# adi-interface_v2.net
KiCad netlist of a schematic drawn in EAGLE
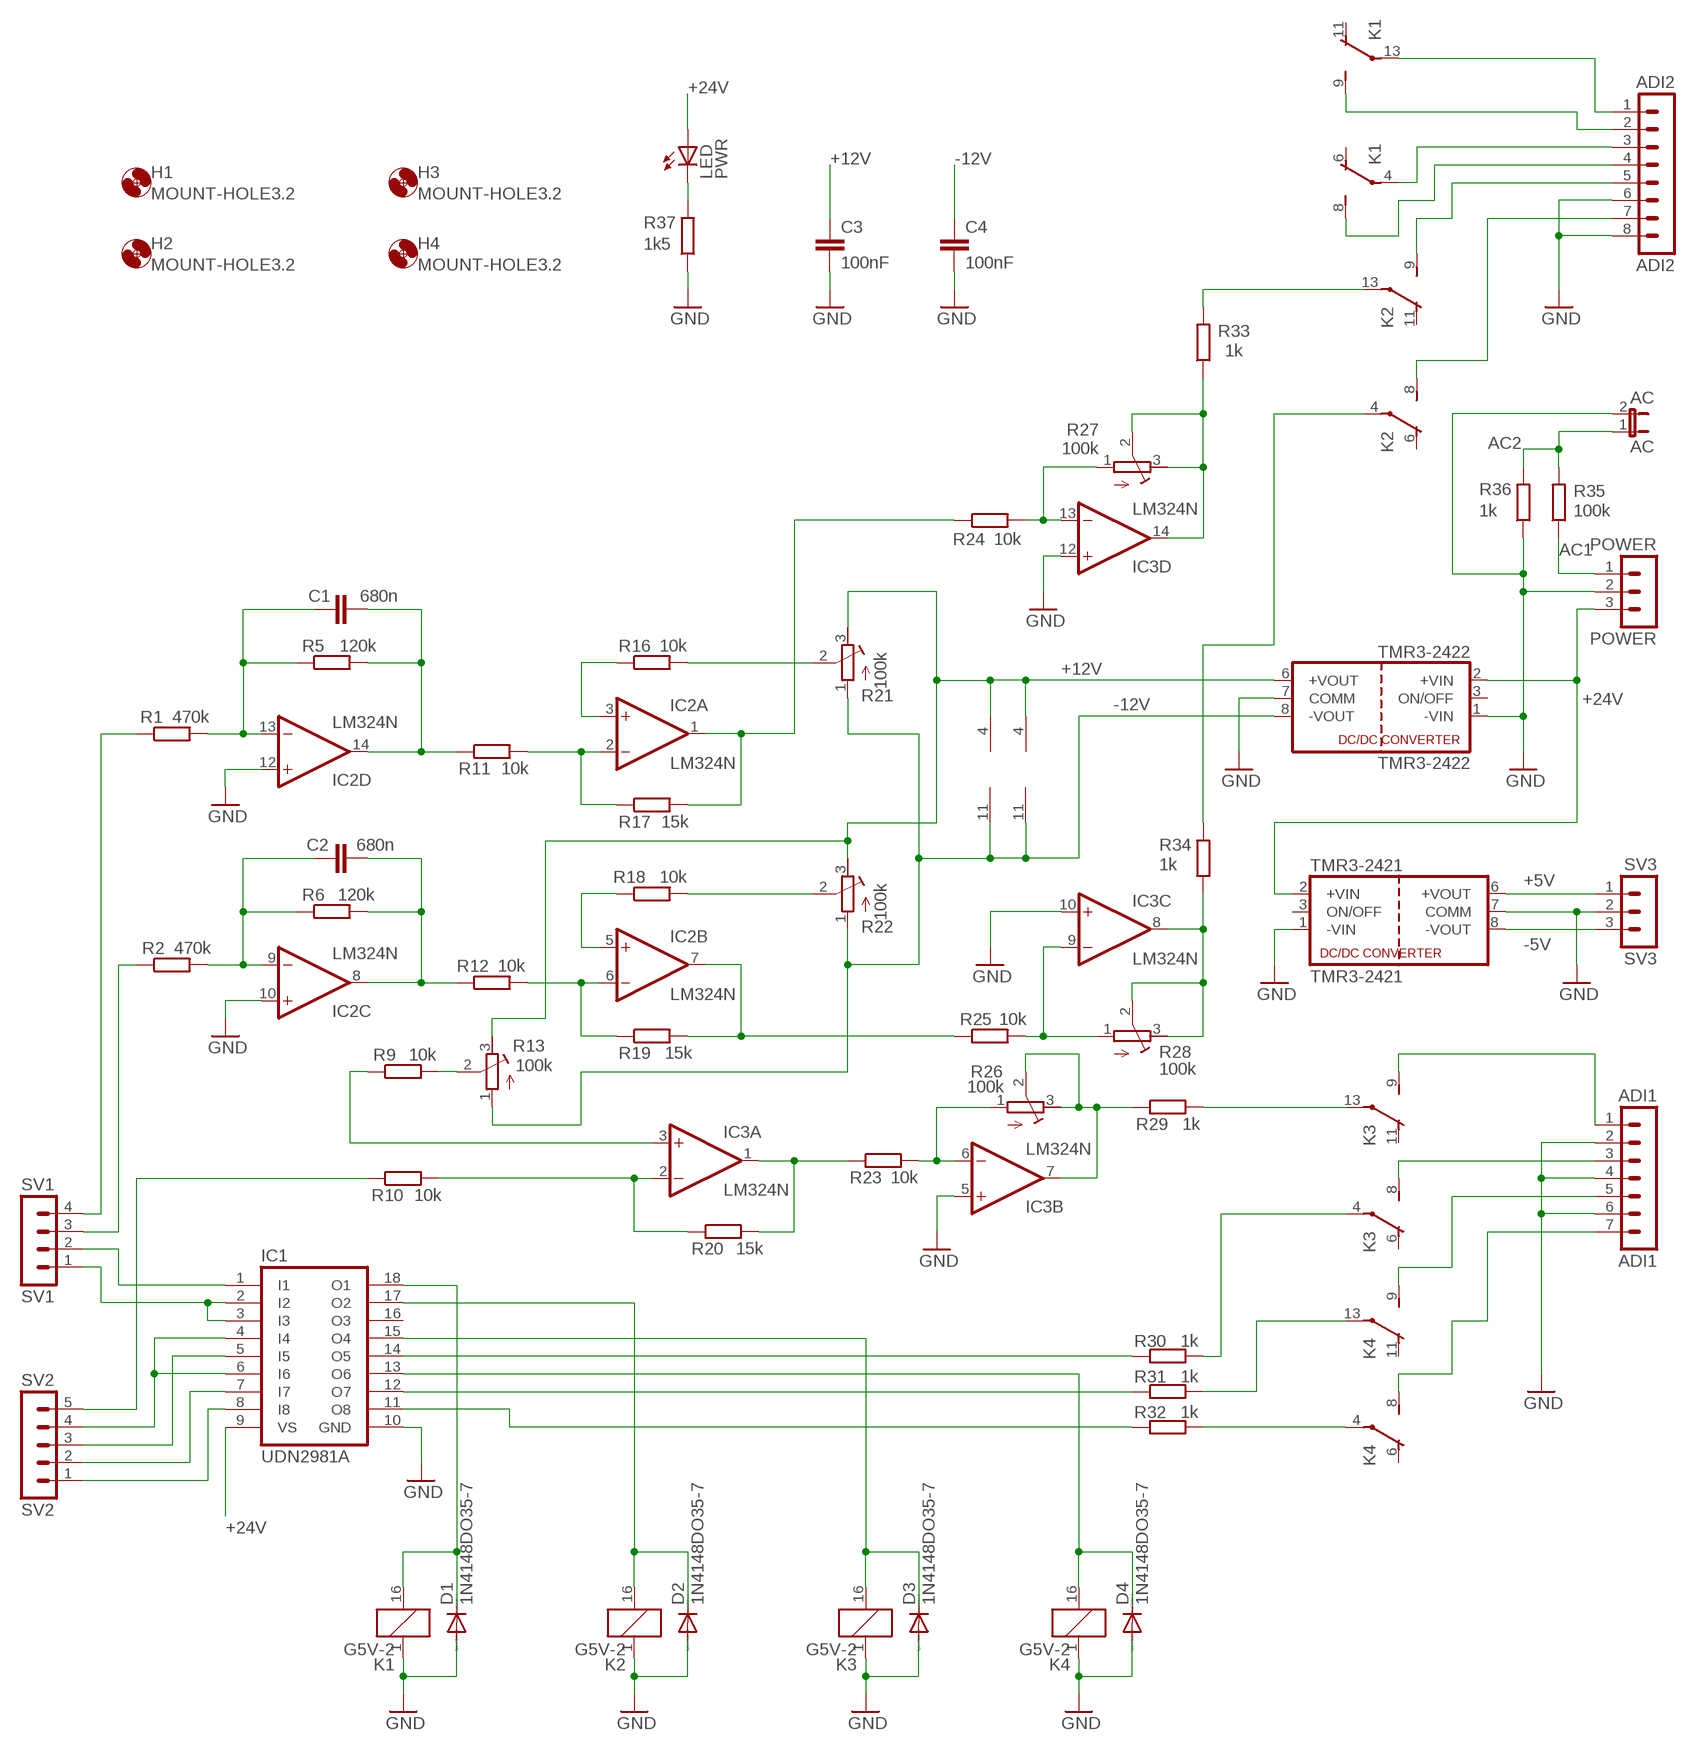
[diagram p0: schematic, sheet 1]
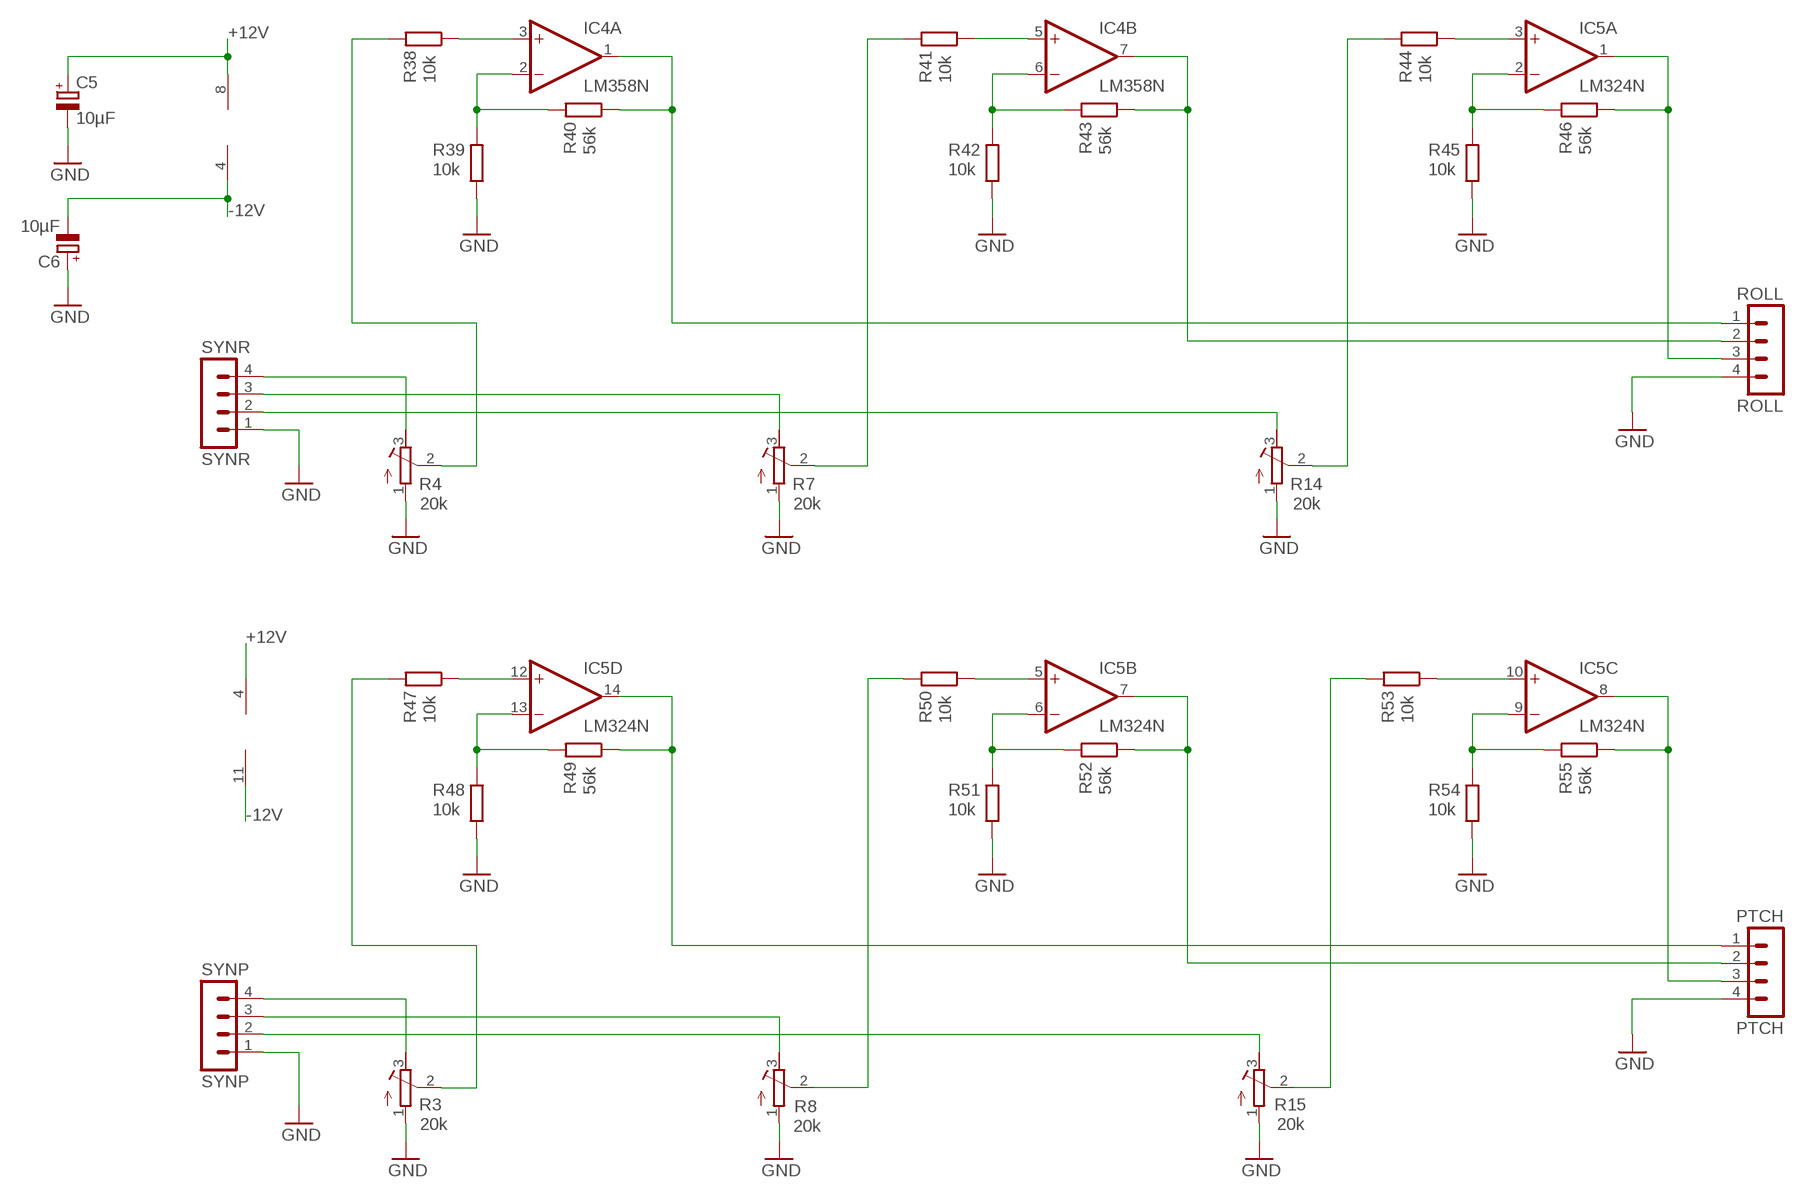
[diagram p1: schematic, sheet 2]

(export (version "E")
  (design (tool "Eeschema 10.0.6"))
  (components
    (comp (ref "AC")
      (value "AC")
      (footprint "eagle-import:1X02")
      (libsource (lib "eagle-import") (part "JUMPER-2PTH"))
    )
    (comp (ref "ADI1")
      (value "ADI1")
      (footprint "eagle-import:MA07-1")
      (libsource (lib "eagle-import") (part "MA07-1"))
    )
    (comp (ref "ADI2")
      (value "ADI2")
      (footprint "eagle-import:MA08-1")
      (libsource (lib "eagle-import") (part "MA08-1"))
    )
    (comp (ref "C1")
      (value "680n")
      (footprint "eagle-import:C050-035X075")
      (libsource (lib "eagle-import") (part "C-EU050-035X075"))
    )
    (comp (ref "C2")
      (value "680n")
      (footprint "eagle-import:C050-035X075")
      (libsource (lib "eagle-import") (part "C-EU050-035X075"))
    )
    (comp (ref "C3")
      (value "100nF")
      (footprint "eagle-import:C025-024X044")
      (libsource (lib "eagle-import") (part "C-EU025-024X044"))
    )
    (comp (ref "C4")
      (value "100nF")
      (footprint "eagle-import:C025-024X044")
      (libsource (lib "eagle-import") (part "C-EU025-024X044"))
    )
    (comp (ref "D1")
      (value "1N4148DO35-7")
      (footprint "eagle-import:DO35-7")
      (libsource (lib "eagle-import") (part "1N4148DO35-7"))
    )
    (comp (ref "D2")
      (value "1N4148DO35-7")
      (footprint "eagle-import:DO35-7")
      (libsource (lib "eagle-import") (part "1N4148DO35-7"))
    )
    (comp (ref "D3")
      (value "1N4148DO35-7")
      (footprint "eagle-import:DO35-7")
      (libsource (lib "eagle-import") (part "1N4148DO35-7"))
    )
    (comp (ref "D4")
      (value "1N4148DO35-7")
      (footprint "eagle-import:DO35-7")
      (libsource (lib "eagle-import") (part "1N4148DO35-7"))
    )
    (comp (ref "H1")
      (value "MOUNT-HOLE3.2")
      (footprint "eagle-import:3,2")
      (libsource (lib "eagle-import") (part "MOUNT-HOLE3.2"))
    )
    (comp (ref "H2")
      (value "MOUNT-HOLE3.2")
      (footprint "eagle-import:3,2")
      (libsource (lib "eagle-import") (part "MOUNT-HOLE3.2"))
    )
    (comp (ref "H3")
      (value "MOUNT-HOLE3.2")
      (footprint "eagle-import:3,2")
      (libsource (lib "eagle-import") (part "MOUNT-HOLE3.2"))
    )
    (comp (ref "H4")
      (value "MOUNT-HOLE3.2")
      (footprint "eagle-import:3,2")
      (libsource (lib "eagle-import") (part "MOUNT-HOLE3.2"))
    )
    (comp (ref "IC1")
      (value "UDN2981A")
      (footprint "eagle-import:DIL18")
      (libsource (lib "eagle-import") (part "UDN298A1"))
    )
    (comp (ref "IC2")
      (value "LM324N")
      (footprint "eagle-import:DIL14")
      (libsource (lib "eagle-import") (part "LM324N"))
    )
    (comp (ref "IC3")
      (value "LM324N")
      (footprint "eagle-import:DIL14")
      (libsource (lib "eagle-import") (part "LM324N"))
    )
    (comp (ref "K1")
      (value "G5V-2")
      (footprint "eagle-import:G5V-2")
      (fields (field (name "MPN") "G5V-2 5DC"))
      (libsource (lib "eagle-import") (part "G5V-2"))
    )
    (comp (ref "K2")
      (value "G5V-2")
      (footprint "eagle-import:G5V-2")
      (fields (field (name "MPN") "G5V-2 5DC"))
      (libsource (lib "eagle-import") (part "G5V-2"))
    )
    (comp (ref "K3")
      (value "G5V-2")
      (footprint "eagle-import:G5V-2")
      (fields (field (name "MPN") "G5V-2 5DC"))
      (libsource (lib "eagle-import") (part "G5V-2"))
    )
    (comp (ref "K4")
      (value "G5V-2")
      (footprint "eagle-import:G5V-2")
      (fields (field (name "MPN") "G5V-2 5DC"))
      (libsource (lib "eagle-import") (part "G5V-2"))
    )
    (comp (ref "LED")
      (value "PWR")
      (footprint "eagle-import:LED3MM")
      (libsource (lib "eagle-import") (part "LED3MM"))
    )
    (comp (ref "POWER")
      (value "POWER")
      (footprint "eagle-import:MA03-1")
      (libsource (lib "eagle-import") (part "MA03-1"))
    )
    (comp (ref "R1")
      (value "470k")
      (footprint "eagle-import:0204_7")
      (libsource (lib "eagle-import") (part "R-EU_0204/7"))
    )
    (comp (ref "R2")
      (value "470k")
      (footprint "eagle-import:0204_7")
      (libsource (lib "eagle-import") (part "R-EU_0204/7"))
    )
    (comp (ref "R5")
      (value "120k")
      (footprint "eagle-import:0204_7")
      (libsource (lib "eagle-import") (part "R-EU_0204/7"))
    )
    (comp (ref "R6")
      (value "120k")
      (footprint "eagle-import:0204_7")
      (libsource (lib "eagle-import") (part "R-EU_0204/7"))
    )
    (comp (ref "R9")
      (value "10k")
      (footprint "eagle-import:0204_7")
      (libsource (lib "eagle-import") (part "R-EU_0204/7"))
    )
    (comp (ref "R10")
      (value "10k")
      (footprint "eagle-import:0204_7")
      (libsource (lib "eagle-import") (part "R-EU_0204/7"))
    )
    (comp (ref "R11")
      (value "10k")
      (footprint "eagle-import:0204_7")
      (libsource (lib "eagle-import") (part "R-EU_0204/7"))
    )
    (comp (ref "R12")
      (value "10k")
      (footprint "eagle-import:0204_7")
      (libsource (lib "eagle-import") (part "R-EU_0204/7"))
    )
    (comp (ref "R13")
      (value "100k")
      (footprint "eagle-import:RTRIM64Z")
      (libsource (lib "eagle-import") (part "R-TRIMM64Z"))
    )
    (comp (ref "R16")
      (value "10k")
      (footprint "eagle-import:0204_7")
      (libsource (lib "eagle-import") (part "R-EU_0204/7"))
    )
    (comp (ref "R17")
      (value "15k")
      (footprint "eagle-import:0204_7")
      (libsource (lib "eagle-import") (part "R-EU_0204/7"))
    )
    (comp (ref "R18")
      (value "10k")
      (footprint "eagle-import:0204_7")
      (libsource (lib "eagle-import") (part "R-EU_0204/7"))
    )
    (comp (ref "R19")
      (value "15k")
      (footprint "eagle-import:0204_7")
      (libsource (lib "eagle-import") (part "R-EU_0204/7"))
    )
    (comp (ref "R20")
      (value "15k")
      (footprint "eagle-import:0204_7")
      (libsource (lib "eagle-import") (part "R-EU_0204/7"))
    )
    (comp (ref "R21")
      (value "100k")
      (footprint "eagle-import:RTRIM64Z")
      (libsource (lib "eagle-import") (part "R-TRIMM64Z"))
    )
    (comp (ref "R22")
      (value "100k")
      (footprint "eagle-import:RTRIM64Z")
      (libsource (lib "eagle-import") (part "R-TRIMM64Z"))
    )
    (comp (ref "R23")
      (value "10k")
      (footprint "eagle-import:0204_7")
      (libsource (lib "eagle-import") (part "R-EU_0204/7"))
    )
    (comp (ref "R24")
      (value "10k")
      (footprint "eagle-import:0204_7")
      (libsource (lib "eagle-import") (part "R-EU_0204/7"))
    )
    (comp (ref "R25")
      (value "10k")
      (footprint "eagle-import:0204_7")
      (libsource (lib "eagle-import") (part "R-EU_0204/7"))
    )
    (comp (ref "R26")
      (value "100k")
      (footprint "eagle-import:RTRIM64Z")
      (libsource (lib "eagle-import") (part "R-TRIMM64Z"))
    )
    (comp (ref "R27")
      (value "100k")
      (footprint "eagle-import:RTRIM64Z")
      (libsource (lib "eagle-import") (part "R-TRIMM64Z"))
    )
    (comp (ref "R28")
      (value "100k")
      (footprint "eagle-import:RTRIM64Z")
      (libsource (lib "eagle-import") (part "R-TRIMM64Z"))
    )
    (comp (ref "R29")
      (value "1k")
      (footprint "eagle-import:0204_7")
      (libsource (lib "eagle-import") (part "R-EU_0204/7"))
    )
    (comp (ref "R30")
      (value "1k")
      (footprint "eagle-import:0204_7")
      (libsource (lib "eagle-import") (part "R-EU_0204/7"))
    )
    (comp (ref "R31")
      (value "1k")
      (footprint "eagle-import:0204_7")
      (libsource (lib "eagle-import") (part "R-EU_0204/7"))
    )
    (comp (ref "R32")
      (value "1k")
      (footprint "eagle-import:0204_7")
      (libsource (lib "eagle-import") (part "R-EU_0204/7"))
    )
    (comp (ref "R33")
      (value "1k")
      (footprint "eagle-import:0204_7")
      (libsource (lib "eagle-import") (part "R-EU_0204/7"))
    )
    (comp (ref "R34")
      (value "1k")
      (footprint "eagle-import:0204_7")
      (libsource (lib "eagle-import") (part "R-EU_0204/7"))
    )
    (comp (ref "R35")
      (value "100k")
      (footprint "eagle-import:0204_7")
      (libsource (lib "eagle-import") (part "R-EU_0204/7"))
    )
    (comp (ref "R36")
      (value "1k")
      (footprint "eagle-import:0204_7")
      (libsource (lib "eagle-import") (part "R-EU_0204/7"))
    )
    (comp (ref "R37")
      (value "1k5")
      (footprint "eagle-import:0204_7")
      (libsource (lib "eagle-import") (part "R-EU_0204/7"))
    )
    (comp (ref "SV1")
      (value "SV1")
      (footprint "eagle-import:MA04-1")
      (libsource (lib "eagle-import") (part "MA04-1"))
    )
    (comp (ref "SV2")
      (value "SV2")
      (footprint "eagle-import:MA05-1")
      (libsource (lib "eagle-import") (part "MA05-1"))
    )
    (comp (ref "SV3")
      (value "SV3")
      (footprint "eagle-import:MA03-1")
      (libsource (lib "eagle-import") (part "MA03-1"))
    )
    (comp (ref "TMR3-2421")
      (value "TMR3-2421")
      (footprint "eagle-import:TRACO_SIP-8")
      (libsource (lib "eagle-import") (part "TMR"))
    )
    (comp (ref "TMR3-2422")
      (value "TMR3-2422")
      (footprint "eagle-import:TRACO_SIP-8")
      (libsource (lib "eagle-import") (part "TMR"))
    )
    (comp (ref "C5")
      (value "10µF")
      (footprint "eagle-import:E2,5-5")
      (libsource (lib "eagle-import") (part "CPOL-EUE2.5-5"))
    )
    (comp (ref "C6")
      (value "10µF")
      (footprint "eagle-import:E2,5-5")
      (libsource (lib "eagle-import") (part "CPOL-EUE2.5-5"))
    )
    (comp (ref "IC4")
      (value "LM358N")
      (footprint "eagle-import:DIL08")
      (libsource (lib "eagle-import") (part "LM358N"))
    )
    (comp (ref "IC5")
      (value "LM324N")
      (footprint "eagle-import:DIL14")
      (libsource (lib "eagle-import") (part "LM324N"))
    )
    (comp (ref "PTCH")
      (value "PTCH")
      (footprint "eagle-import:MA04-1")
      (libsource (lib "eagle-import") (part "MA04-1"))
    )
    (comp (ref "R3")
      (value "20k")
      (footprint "eagle-import:RTRIM64Z")
      (libsource (lib "eagle-import") (part "R-TRIMM64Z"))
    )
    (comp (ref "R4")
      (value "20k")
      (footprint "eagle-import:RTRIM64Z")
      (libsource (lib "eagle-import") (part "R-TRIMM64Z"))
    )
    (comp (ref "R7")
      (value "20k")
      (footprint "eagle-import:RTRIM64Z")
      (libsource (lib "eagle-import") (part "R-TRIMM64Z"))
    )
    (comp (ref "R8")
      (value "20k")
      (footprint "eagle-import:RTRIM64Z")
      (libsource (lib "eagle-import") (part "R-TRIMM64Z"))
    )
    (comp (ref "R14")
      (value "20k")
      (footprint "eagle-import:RTRIM64Z")
      (libsource (lib "eagle-import") (part "R-TRIMM64Z"))
    )
    (comp (ref "R15")
      (value "20k")
      (footprint "eagle-import:RTRIM64Z")
      (libsource (lib "eagle-import") (part "R-TRIMM64Z"))
    )
    (comp (ref "R38")
      (value "10k")
      (footprint "eagle-import:0204_7")
      (libsource (lib "eagle-import") (part "R-EU_0204/7"))
    )
    (comp (ref "R39")
      (value "10k")
      (footprint "eagle-import:0204_7")
      (libsource (lib "eagle-import") (part "R-EU_0204/7"))
    )
    (comp (ref "R40")
      (value "56k")
      (footprint "eagle-import:0204_7")
      (libsource (lib "eagle-import") (part "R-EU_0204/7"))
    )
    (comp (ref "R41")
      (value "10k")
      (footprint "eagle-import:0204_7")
      (libsource (lib "eagle-import") (part "R-EU_0204/7"))
    )
    (comp (ref "R42")
      (value "10k")
      (footprint "eagle-import:0204_7")
      (libsource (lib "eagle-import") (part "R-EU_0204/7"))
    )
    (comp (ref "R43")
      (value "56k")
      (footprint "eagle-import:0204_7")
      (libsource (lib "eagle-import") (part "R-EU_0204/7"))
    )
    (comp (ref "R44")
      (value "10k")
      (footprint "eagle-import:0204_7")
      (libsource (lib "eagle-import") (part "R-EU_0204/7"))
    )
    (comp (ref "R45")
      (value "10k")
      (footprint "eagle-import:0204_7")
      (libsource (lib "eagle-import") (part "R-EU_0204/7"))
    )
    (comp (ref "R46")
      (value "56k")
      (footprint "eagle-import:0204_7")
      (libsource (lib "eagle-import") (part "R-EU_0204/7"))
    )
    (comp (ref "R47")
      (value "10k")
      (footprint "eagle-import:0204_7")
      (libsource (lib "eagle-import") (part "R-EU_0204/7"))
    )
    (comp (ref "R48")
      (value "10k")
      (footprint "eagle-import:0204_7")
      (libsource (lib "eagle-import") (part "R-EU_0204/7"))
    )
    (comp (ref "R49")
      (value "56k")
      (footprint "eagle-import:0204_7")
      (libsource (lib "eagle-import") (part "R-EU_0204/7"))
    )
    (comp (ref "R50")
      (value "10k")
      (footprint "eagle-import:0204_7")
      (libsource (lib "eagle-import") (part "R-EU_0204/7"))
    )
    (comp (ref "R51")
      (value "10k")
      (footprint "eagle-import:0204_7")
      (libsource (lib "eagle-import") (part "R-EU_0204/7"))
    )
    (comp (ref "R52")
      (value "56k")
      (footprint "eagle-import:0204_7")
      (libsource (lib "eagle-import") (part "R-EU_0204/7"))
    )
    (comp (ref "R53")
      (value "10k")
      (footprint "eagle-import:0204_7")
      (libsource (lib "eagle-import") (part "R-EU_0204/7"))
    )
    (comp (ref "R54")
      (value "10k")
      (footprint "eagle-import:0204_7")
      (libsource (lib "eagle-import") (part "R-EU_0204/7"))
    )
    (comp (ref "R55")
      (value "56k")
      (footprint "eagle-import:0204_7")
      (libsource (lib "eagle-import") (part "R-EU_0204/7"))
    )
    (comp (ref "ROLL")
      (value "ROLL")
      (footprint "eagle-import:MA04-1")
      (libsource (lib "eagle-import") (part "MA04-1"))
    )
    (comp (ref "SYNP")
      (value "SYNP")
      (footprint "eagle-import:MA04-1")
      (libsource (lib "eagle-import") (part "MA04-1"))
    )
    (comp (ref "SYNR")
      (value "SYNR")
      (footprint "eagle-import:MA04-1")
      (libsource (lib "eagle-import") (part "MA04-1"))
    )
  )
  (nets
    (net (code "1") (name "+5V") (class "Default")
      (node (ref "SV3") (pin "1") (pinfunction "1_1") (pintype "passive"))
      (node (ref "TMR3-2421") (pin "6") (pinfunction "+VOUT_6") (pintype "passive"))
    )
    (net (code "2") (name "+12V") (class "Default")
      (node (ref "C3") (pin "1") (pinfunction "1_1") (pintype "passive"))
      (node (ref "C5") (pin "+") (pinfunction "+_+") (pintype "passive"))
      (node (ref "IC2") (pin "4") (pinfunction "V+_4") (pintype "power_in"))
      (node (ref "IC3") (pin "4") (pinfunction "V+_4") (pintype "power_in"))
      (node (ref "IC4") (pin "8") (pinfunction "V+_8") (pintype "power_in"))
      (node (ref "IC5") (pin "4") (pinfunction "V+_4") (pintype "power_in"))
      (node (ref "R13") (pin "3") (pinfunction "E_3") (pintype "passive"))
      (node (ref "R21") (pin "3") (pinfunction "E_3") (pintype "passive"))
      (node (ref "R22") (pin "3") (pinfunction "E_3") (pintype "passive"))
      (node (ref "TMR3-2422") (pin "6") (pinfunction "+VOUT_6") (pintype "passive"))
    )
    (net (code "3") (name "+24V") (class "Default")
      (node (ref "IC1") (pin "9") (pinfunction "VS_9") (pintype "passive"))
      (node (ref "LED") (pin "A") (pinfunction "A_A") (pintype "passive"))
      (node (ref "POWER") (pin "3") (pinfunction "3_3") (pintype "passive"))
      (node (ref "TMR3-2421") (pin "2") (pinfunction "+VIN_2") (pintype "passive"))
      (node (ref "TMR3-2422") (pin "2") (pinfunction "+VIN_2") (pintype "passive"))
    )
    (net (code "4") (name "-5V") (class "Default")
      (node (ref "SV3") (pin "3") (pinfunction "3_3") (pintype "passive"))
      (node (ref "TMR3-2421") (pin "8") (pinfunction "-VOUT_8") (pintype "passive"))
    )
    (net (code "5") (name "-12V") (class "Default")
      (node (ref "C4") (pin "1") (pinfunction "1_1") (pintype "passive"))
      (node (ref "C6") (pin "-") (pinfunction "-_-") (pintype "passive"))
      (node (ref "IC2") (pin "11") (pinfunction "V-_11") (pintype "power_in"))
      (node (ref "IC3") (pin "11") (pinfunction "V-_11") (pintype "power_in"))
      (node (ref "IC4") (pin "4") (pinfunction "V-_4") (pintype "power_in"))
      (node (ref "IC5") (pin "11") (pinfunction "V-_11") (pintype "power_in"))
      (node (ref "R13") (pin "1") (pinfunction "A_1") (pintype "passive"))
      (node (ref "R21") (pin "1") (pinfunction "A_1") (pintype "passive"))
      (node (ref "R22") (pin "1") (pinfunction "A_1") (pintype "passive"))
      (node (ref "TMR3-2422") (pin "8") (pinfunction "-VOUT_8") (pintype "passive"))
    )
    (net (code "6") (name "AC1") (class "Default")
      (node (ref "POWER") (pin "1") (pinfunction "1_1") (pintype "passive"))
      (node (ref "R35") (pin "1") (pinfunction "1_1") (pintype "passive"))
    )
    (net (code "7") (name "AC2") (class "Default")
      (node (ref "AC") (pin "1") (pinfunction "1_1") (pintype "passive"))
      (node (ref "R35") (pin "2") (pinfunction "2_2") (pintype "passive"))
      (node (ref "R36") (pin "2") (pinfunction "2_2") (pintype "passive"))
    )
    (net (code "8") (name "GND") (class "Default")
      (node (ref "AC") (pin "2") (pinfunction "2_2") (pintype "passive"))
      (node (ref "ADI1") (pin "2") (pinfunction "2_2") (pintype "passive"))
      (node (ref "ADI1") (pin "4") (pinfunction "4_4") (pintype "passive"))
      (node (ref "ADI1") (pin "6") (pinfunction "6_6") (pintype "passive"))
      (node (ref "ADI2") (pin "6") (pinfunction "6_6") (pintype "passive"))
      (node (ref "ADI2") (pin "8") (pinfunction "8_8") (pintype "passive"))
      (node (ref "C3") (pin "2") (pinfunction "2_2") (pintype "passive"))
      (node (ref "C4") (pin "2") (pinfunction "2_2") (pintype "passive"))
      (node (ref "C5") (pin "-") (pinfunction "-_-") (pintype "passive"))
      (node (ref "C6") (pin "+") (pinfunction "+_+") (pintype "passive"))
      (node (ref "D1") (pin "A") (pinfunction "A_A") (pintype "passive"))
      (node (ref "D2") (pin "A") (pinfunction "A_A") (pintype "passive"))
      (node (ref "D3") (pin "A") (pinfunction "A_A") (pintype "passive"))
      (node (ref "D4") (pin "A") (pinfunction "A_A") (pintype "passive"))
      (node (ref "IC1") (pin "10") (pinfunction "GND_10") (pintype "power_in"))
      (node (ref "IC2") (pin "10") (pinfunction "+IN_10") (pintype "input"))
      (node (ref "IC2") (pin "12") (pinfunction "+IN_12") (pintype "input"))
      (node (ref "IC3") (pin "10") (pinfunction "+IN_10") (pintype "input"))
      (node (ref "IC3") (pin "12") (pinfunction "+IN_12") (pintype "input"))
      (node (ref "IC3") (pin "5") (pinfunction "+IN_5") (pintype "input"))
      (node (ref "K1") (pin "1") (pinfunction "1_1") (pintype "passive"))
      (node (ref "K2") (pin "1") (pinfunction "1_1") (pintype "passive"))
      (node (ref "K3") (pin "1") (pinfunction "1_1") (pintype "passive"))
      (node (ref "K4") (pin "1") (pinfunction "1_1") (pintype "passive"))
      (node (ref "POWER") (pin "2") (pinfunction "2_2") (pintype "passive"))
      (node (ref "PTCH") (pin "4") (pinfunction "4_4") (pintype "passive"))
      (node (ref "R14") (pin "1") (pinfunction "A_1") (pintype "passive"))
      (node (ref "R15") (pin "1") (pinfunction "A_1") (pintype "passive"))
      (node (ref "R3") (pin "1") (pinfunction "A_1") (pintype "passive"))
      (node (ref "R36") (pin "1") (pinfunction "1_1") (pintype "passive"))
      (node (ref "R37") (pin "1") (pinfunction "1_1") (pintype "passive"))
      (node (ref "R39") (pin "1") (pinfunction "1_1") (pintype "passive"))
      (node (ref "R4") (pin "1") (pinfunction "A_1") (pintype "passive"))
      (node (ref "R42") (pin "1") (pinfunction "1_1") (pintype "passive"))
      (node (ref "R45") (pin "1") (pinfunction "1_1") (pintype "passive"))
      (node (ref "R48") (pin "1") (pinfunction "1_1") (pintype "passive"))
      (node (ref "R51") (pin "1") (pinfunction "1_1") (pintype "passive"))
      (node (ref "R54") (pin "1") (pinfunction "1_1") (pintype "passive"))
      (node (ref "R7") (pin "1") (pinfunction "A_1") (pintype "passive"))
      (node (ref "R8") (pin "1") (pinfunction "A_1") (pintype "passive"))
      (node (ref "ROLL") (pin "4") (pinfunction "4_4") (pintype "passive"))
      (node (ref "SV3") (pin "2") (pinfunction "2_2") (pintype "passive"))
      (node (ref "SYNP") (pin "1") (pinfunction "1_1") (pintype "passive"))
      (node (ref "SYNR") (pin "1") (pinfunction "1_1") (pintype "passive"))
      (node (ref "TMR3-2421") (pin "1") (pinfunction "-VIN_1") (pintype "passive"))
      (node (ref "TMR3-2421") (pin "7") (pinfunction "COMM_7") (pintype "passive"))
      (node (ref "TMR3-2422") (pin "1") (pinfunction "-VIN_1") (pintype "passive"))
      (node (ref "TMR3-2422") (pin "7") (pinfunction "COMM_7") (pintype "passive"))
    )
    (net (code "9") (name "Net-(IC1-I1)") (class "Default")
      (node (ref "IC1") (pin "1") (pinfunction "I1_1") (pintype "input"))
      (node (ref "SV1") (pin "2") (pinfunction "2_2") (pintype "passive"))
    )
    (net (code "10") (name "Net-(IC1-I2)") (class "Default")
      (node (ref "IC1") (pin "2") (pinfunction "I2_2") (pintype "input"))
      (node (ref "IC1") (pin "3") (pinfunction "I3_3") (pintype "input"))
      (node (ref "SV1") (pin "1") (pinfunction "1_1") (pintype "passive"))
    )
    (net (code "11") (name "Net-(IC1-I4)") (class "Default")
      (node (ref "IC1") (pin "4") (pinfunction "I4_4") (pintype "input"))
      (node (ref "IC1") (pin "6") (pinfunction "I6_6") (pintype "input"))
      (node (ref "SV2") (pin "4") (pinfunction "4_4") (pintype "passive"))
    )
    (net (code "12") (name "Net-(IC1-I5)") (class "Default")
      (node (ref "IC1") (pin "5") (pinfunction "I5_5") (pintype "input"))
      (node (ref "SV2") (pin "3") (pinfunction "3_3") (pintype "passive"))
    )
    (net (code "13") (name "Net-(IC1-I7)") (class "Default")
      (node (ref "IC1") (pin "7") (pinfunction "I7_7") (pintype "input"))
      (node (ref "SV2") (pin "2") (pinfunction "2_2") (pintype "passive"))
    )
    (net (code "14") (name "Net-(IC1-I8)") (class "Default")
      (node (ref "IC1") (pin "8") (pinfunction "I8_8") (pintype "input"))
      (node (ref "SV2") (pin "1") (pinfunction "1_1") (pintype "passive"))
    )
    (net (code "15") (name "Net-(IC1-O1)") (class "Default")
      (node (ref "D1") (pin "C") (pinfunction "C_C") (pintype "passive"))
      (node (ref "IC1") (pin "18") (pinfunction "O1_18") (pintype "open_collector"))
      (node (ref "K1") (pin "16") (pinfunction "2_16") (pintype "passive"))
    )
    (net (code "16") (name "Net-(IC1-O2)") (class "Default")
      (node (ref "D2") (pin "C") (pinfunction "C_C") (pintype "passive"))
      (node (ref "IC1") (pin "17") (pinfunction "O2_17") (pintype "open_collector"))
      (node (ref "K2") (pin "16") (pinfunction "2_16") (pintype "passive"))
    )
    (net (code "17") (name "Net-(IC1-O4)") (class "Default")
      (node (ref "D3") (pin "C") (pinfunction "C_C") (pintype "passive"))
      (node (ref "IC1") (pin "15") (pinfunction "O4_15") (pintype "open_collector"))
      (node (ref "K3") (pin "16") (pinfunction "2_16") (pintype "passive"))
    )
    (net (code "18") (name "Net-(IC1-O5)") (class "Default")
      (node (ref "IC1") (pin "14") (pinfunction "O5_14") (pintype "open_collector"))
      (node (ref "R30") (pin "1") (pinfunction "1_1") (pintype "passive"))
    )
    (net (code "19") (name "Net-(IC1-O6)") (class "Default")
      (node (ref "D4") (pin "C") (pinfunction "C_C") (pintype "passive"))
      (node (ref "IC1") (pin "13") (pinfunction "O6_13") (pintype "open_collector"))
      (node (ref "K4") (pin "16") (pinfunction "2_16") (pintype "passive"))
    )
    (net (code "20") (name "Net-(IC1-O7)") (class "Default")
      (node (ref "IC1") (pin "12") (pinfunction "O7_12") (pintype "open_collector"))
      (node (ref "R31") (pin "1") (pinfunction "1_1") (pintype "passive"))
    )
    (net (code "21") (name "Net-(IC1-O8)") (class "Default")
      (node (ref "IC1") (pin "11") (pinfunction "O8_11") (pintype "open_collector"))
      (node (ref "R32") (pin "1") (pinfunction "1_1") (pintype "passive"))
    )
    (net (code "22") (name "Net-(IC2A-+IN)") (class "Default")
      (node (ref "IC2") (pin "3") (pinfunction "+IN_3") (pintype "input"))
      (node (ref "R16") (pin "1") (pinfunction "1_1") (pintype "passive"))
    )
    (net (code "23") (name "Net-(IC2A--IN)") (class "Default")
      (node (ref "IC2") (pin "2") (pinfunction "-IN_2") (pintype "input"))
      (node (ref "R11") (pin "2") (pinfunction "2_2") (pintype "passive"))
      (node (ref "R17") (pin "1") (pinfunction "1_1") (pintype "passive"))
    )
    (net (code "24") (name "Net-(IC2A-OUT)") (class "Default")
      (node (ref "IC2") (pin "1") (pinfunction "OUT_1") (pintype "output"))
      (node (ref "R17") (pin "2") (pinfunction "2_2") (pintype "passive"))
      (node (ref "R24") (pin "1") (pinfunction "1_1") (pintype "passive"))
    )
    (net (code "25") (name "Net-(IC2B-+IN)") (class "Default")
      (node (ref "IC2") (pin "5") (pinfunction "+IN_5") (pintype "input"))
      (node (ref "R18") (pin "1") (pinfunction "1_1") (pintype "passive"))
    )
    (net (code "26") (name "Net-(IC2B--IN)") (class "Default")
      (node (ref "IC2") (pin "6") (pinfunction "-IN_6") (pintype "input"))
      (node (ref "R12") (pin "2") (pinfunction "2_2") (pintype "passive"))
      (node (ref "R19") (pin "1") (pinfunction "1_1") (pintype "passive"))
    )
    (net (code "27") (name "Net-(IC2B-OUT)") (class "Default")
      (node (ref "IC2") (pin "7") (pinfunction "OUT_7") (pintype "output"))
      (node (ref "R19") (pin "2") (pinfunction "2_2") (pintype "passive"))
      (node (ref "R25") (pin "1") (pinfunction "1_1") (pintype "passive"))
    )
    (net (code "28") (name "Net-(IC2C--IN)") (class "Default")
      (node (ref "C2") (pin "1") (pinfunction "1_1") (pintype "passive"))
      (node (ref "IC2") (pin "9") (pinfunction "-IN_9") (pintype "input"))
      (node (ref "R2") (pin "2") (pinfunction "2_2") (pintype "passive"))
      (node (ref "R6") (pin "1") (pinfunction "1_1") (pintype "passive"))
    )
    (net (code "29") (name "Net-(IC2C-OUT)") (class "Default")
      (node (ref "C2") (pin "2") (pinfunction "2_2") (pintype "passive"))
      (node (ref "IC2") (pin "8") (pinfunction "OUT_8") (pintype "output"))
      (node (ref "R12") (pin "1") (pinfunction "1_1") (pintype "passive"))
      (node (ref "R6") (pin "2") (pinfunction "2_2") (pintype "passive"))
    )
    (net (code "30") (name "Net-(IC2D--IN)") (class "Default")
      (node (ref "C1") (pin "1") (pinfunction "1_1") (pintype "passive"))
      (node (ref "IC2") (pin "13") (pinfunction "-IN_13") (pintype "input"))
      (node (ref "R1") (pin "2") (pinfunction "2_2") (pintype "passive"))
      (node (ref "R5") (pin "1") (pinfunction "1_1") (pintype "passive"))
    )
    (net (code "31") (name "Net-(IC2D-OUT)") (class "Default")
      (node (ref "C1") (pin "2") (pinfunction "2_2") (pintype "passive"))
      (node (ref "IC2") (pin "14") (pinfunction "OUT_14") (pintype "output"))
      (node (ref "R11") (pin "1") (pinfunction "1_1") (pintype "passive"))
      (node (ref "R5") (pin "2") (pinfunction "2_2") (pintype "passive"))
    )
    (net (code "32") (name "Net-(IC3A-+IN)") (class "Default")
      (node (ref "IC3") (pin "3") (pinfunction "+IN_3") (pintype "input"))
      (node (ref "R9") (pin "1") (pinfunction "1_1") (pintype "passive"))
    )
    (net (code "33") (name "Net-(IC3A--IN)") (class "Default")
      (node (ref "IC3") (pin "2") (pinfunction "-IN_2") (pintype "input"))
      (node (ref "R10") (pin "2") (pinfunction "2_2") (pintype "passive"))
      (node (ref "R20") (pin "1") (pinfunction "1_1") (pintype "passive"))
    )
    (net (code "34") (name "Net-(IC3A-OUT)") (class "Default")
      (node (ref "IC3") (pin "1") (pinfunction "OUT_1") (pintype "output"))
      (node (ref "R20") (pin "2") (pinfunction "2_2") (pintype "passive"))
      (node (ref "R23") (pin "1") (pinfunction "1_1") (pintype "passive"))
    )
    (net (code "35") (name "Net-(IC3B--IN)") (class "Default")
      (node (ref "IC3") (pin "6") (pinfunction "-IN_6") (pintype "input"))
      (node (ref "R23") (pin "2") (pinfunction "2_2") (pintype "passive"))
      (node (ref "R26") (pin "1") (pinfunction "A_1") (pintype "passive"))
    )
    (net (code "36") (name "Net-(IC3B-OUT)") (class "Default")
      (node (ref "IC3") (pin "7") (pinfunction "OUT_7") (pintype "output"))
      (node (ref "R26") (pin "2") (pinfunction "S_2") (pintype "passive"))
      (node (ref "R26") (pin "3") (pinfunction "E_3") (pintype "passive"))
      (node (ref "R29") (pin "1") (pinfunction "1_1") (pintype "passive"))
    )
    (net (code "37") (name "Net-(IC3C--IN)") (class "Default")
      (node (ref "IC3") (pin "9") (pinfunction "-IN_9") (pintype "input"))
      (node (ref "R25") (pin "2") (pinfunction "2_2") (pintype "passive"))
      (node (ref "R28") (pin "1") (pinfunction "A_1") (pintype "passive"))
    )
    (net (code "38") (name "Net-(IC3C-OUT)") (class "Default")
      (node (ref "IC3") (pin "8") (pinfunction "OUT_8") (pintype "output"))
      (node (ref "R28") (pin "2") (pinfunction "S_2") (pintype "passive"))
      (node (ref "R28") (pin "3") (pinfunction "E_3") (pintype "passive"))
      (node (ref "R34") (pin "1") (pinfunction "1_1") (pintype "passive"))
    )
    (net (code "39") (name "Net-(IC3D--IN)") (class "Default")
      (node (ref "IC3") (pin "13") (pinfunction "-IN_13") (pintype "input"))
      (node (ref "R24") (pin "2") (pinfunction "2_2") (pintype "passive"))
      (node (ref "R27") (pin "1") (pinfunction "A_1") (pintype "passive"))
    )
    (net (code "40") (name "Net-(IC3D-OUT)") (class "Default")
      (node (ref "IC3") (pin "14") (pinfunction "OUT_14") (pintype "output"))
      (node (ref "R27") (pin "2") (pinfunction "S_2") (pintype "passive"))
      (node (ref "R27") (pin "3") (pinfunction "E_3") (pintype "passive"))
      (node (ref "R33") (pin "1") (pinfunction "1_1") (pintype "passive"))
    )
    (net (code "41") (name "Net-(IC4A-+IN)") (class "Default")
      (node (ref "IC4") (pin "3") (pinfunction "+IN_3") (pintype "input"))
      (node (ref "R38") (pin "1") (pinfunction "1_1") (pintype "passive"))
    )
    (net (code "42") (name "Net-(IC4A--IN)") (class "Default")
      (node (ref "IC4") (pin "2") (pinfunction "-IN_2") (pintype "input"))
      (node (ref "R39") (pin "2") (pinfunction "2_2") (pintype "passive"))
      (node (ref "R40") (pin "2") (pinfunction "2_2") (pintype "passive"))
    )
    (net (code "43") (name "Net-(IC4A-OUT)") (class "Default")
      (node (ref "IC4") (pin "1") (pinfunction "OUT_1") (pintype "output"))
      (node (ref "R40") (pin "1") (pinfunction "1_1") (pintype "passive"))
      (node (ref "ROLL") (pin "1") (pinfunction "1_1") (pintype "passive"))
    )
    (net (code "44") (name "Net-(IC4B-+IN)") (class "Default")
      (node (ref "IC4") (pin "5") (pinfunction "+IN_5") (pintype "input"))
      (node (ref "R41") (pin "1") (pinfunction "1_1") (pintype "passive"))
    )
    (net (code "45") (name "Net-(IC4B--IN)") (class "Default")
      (node (ref "IC4") (pin "6") (pinfunction "-IN_6") (pintype "input"))
      (node (ref "R42") (pin "2") (pinfunction "2_2") (pintype "passive"))
      (node (ref "R43") (pin "2") (pinfunction "2_2") (pintype "passive"))
    )
    (net (code "46") (name "Net-(IC4B-OUT)") (class "Default")
      (node (ref "IC4") (pin "7") (pinfunction "OUT_7") (pintype "output"))
      (node (ref "R43") (pin "1") (pinfunction "1_1") (pintype "passive"))
      (node (ref "ROLL") (pin "2") (pinfunction "2_2") (pintype "passive"))
    )
    (net (code "47") (name "Net-(IC5A-+IN)") (class "Default")
      (node (ref "IC5") (pin "3") (pinfunction "+IN_3") (pintype "input"))
      (node (ref "R44") (pin "1") (pinfunction "1_1") (pintype "passive"))
    )
    (net (code "48") (name "Net-(IC5A--IN)") (class "Default")
      (node (ref "IC5") (pin "2") (pinfunction "-IN_2") (pintype "input"))
      (node (ref "R45") (pin "2") (pinfunction "2_2") (pintype "passive"))
      (node (ref "R46") (pin "2") (pinfunction "2_2") (pintype "passive"))
    )
    (net (code "49") (name "Net-(IC5A-OUT)") (class "Default")
      (node (ref "IC5") (pin "1") (pinfunction "OUT_1") (pintype "output"))
      (node (ref "R46") (pin "1") (pinfunction "1_1") (pintype "passive"))
      (node (ref "ROLL") (pin "3") (pinfunction "3_3") (pintype "passive"))
    )
    (net (code "50") (name "Net-(IC5B-+IN)") (class "Default")
      (node (ref "IC5") (pin "5") (pinfunction "+IN_5") (pintype "input"))
      (node (ref "R50") (pin "1") (pinfunction "1_1") (pintype "passive"))
    )
    (net (code "51") (name "Net-(IC5B--IN)") (class "Default")
      (node (ref "IC5") (pin "6") (pinfunction "-IN_6") (pintype "input"))
      (node (ref "R51") (pin "2") (pinfunction "2_2") (pintype "passive"))
      (node (ref "R52") (pin "2") (pinfunction "2_2") (pintype "passive"))
    )
    (net (code "52") (name "Net-(IC5B-OUT)") (class "Default")
      (node (ref "IC5") (pin "7") (pinfunction "OUT_7") (pintype "output"))
      (node (ref "PTCH") (pin "2") (pinfunction "2_2") (pintype "passive"))
      (node (ref "R52") (pin "1") (pinfunction "1_1") (pintype "passive"))
    )
    (net (code "53") (name "Net-(IC5C-+IN)") (class "Default")
      (node (ref "IC5") (pin "10") (pinfunction "+IN_10") (pintype "input"))
      (node (ref "R53") (pin "1") (pinfunction "1_1") (pintype "passive"))
    )
    (net (code "54") (name "Net-(IC5C--IN)") (class "Default")
      (node (ref "IC5") (pin "9") (pinfunction "-IN_9") (pintype "input"))
      (node (ref "R54") (pin "2") (pinfunction "2_2") (pintype "passive"))
      (node (ref "R55") (pin "2") (pinfunction "2_2") (pintype "passive"))
    )
    (net (code "55") (name "Net-(IC5C-OUT)") (class "Default")
      (node (ref "IC5") (pin "8") (pinfunction "OUT_8") (pintype "output"))
      (node (ref "PTCH") (pin "3") (pinfunction "3_3") (pintype "passive"))
      (node (ref "R55") (pin "1") (pinfunction "1_1") (pintype "passive"))
    )
    (net (code "56") (name "Net-(IC5D-+IN)") (class "Default")
      (node (ref "IC5") (pin "12") (pinfunction "+IN_12") (pintype "input"))
      (node (ref "R47") (pin "1") (pinfunction "1_1") (pintype "passive"))
    )
    (net (code "57") (name "Net-(IC5D--IN)") (class "Default")
      (node (ref "IC5") (pin "13") (pinfunction "-IN_13") (pintype "input"))
      (node (ref "R48") (pin "2") (pinfunction "2_2") (pintype "passive"))
      (node (ref "R49") (pin "2") (pinfunction "2_2") (pintype "passive"))
    )
    (net (code "58") (name "Net-(IC5D-OUT)") (class "Default")
      (node (ref "IC5") (pin "14") (pinfunction "OUT_14") (pintype "output"))
      (node (ref "PTCH") (pin "1") (pinfunction "1_1") (pintype "passive"))
      (node (ref "R49") (pin "1") (pinfunction "1_1") (pintype "passive"))
    )
    (net (code "59") (name "Net-(K1A-P)") (class "Default")
      (node (ref "ADI2") (pin "3") (pinfunction "3_3") (pintype "passive"))
      (node (ref "K1") (pin "4") (pinfunction "P_4") (pintype "passive"))
    )
    (net (code "60") (name "Net-(K1A-S)") (class "Default")
      (node (ref "ADI2") (pin "4") (pinfunction "4_4") (pintype "passive"))
      (node (ref "K1") (pin "8") (pinfunction "S_8") (pintype "passive"))
    )
    (net (code "61") (name "Net-(K1B-P)") (class "Default")
      (node (ref "ADI2") (pin "1") (pinfunction "1_1") (pintype "passive"))
      (node (ref "K1") (pin "13") (pinfunction "P_13") (pintype "passive"))
    )
    (net (code "62") (name "Net-(K1B-S)") (class "Default")
      (node (ref "ADI2") (pin "2") (pinfunction "2_2") (pintype "passive"))
      (node (ref "K1") (pin "9") (pinfunction "S_9") (pintype "passive"))
    )
    (net (code "63") (name "Net-(K2A-P)") (class "Default")
      (node (ref "K2") (pin "4") (pinfunction "P_4") (pintype "passive"))
      (node (ref "R34") (pin "2") (pinfunction "2_2") (pintype "passive"))
    )
    (net (code "64") (name "Net-(K2A-S)") (class "Default")
      (node (ref "ADI2") (pin "7") (pinfunction "7_7") (pintype "passive"))
      (node (ref "K2") (pin "8") (pinfunction "S_8") (pintype "passive"))
    )
    (net (code "65") (name "Net-(K2B-P)") (class "Default")
      (node (ref "K2") (pin "13") (pinfunction "P_13") (pintype "passive"))
      (node (ref "R33") (pin "2") (pinfunction "2_2") (pintype "passive"))
    )
    (net (code "66") (name "Net-(K2B-S)") (class "Default")
      (node (ref "ADI2") (pin "5") (pinfunction "5_5") (pintype "passive"))
      (node (ref "K2") (pin "9") (pinfunction "S_9") (pintype "passive"))
    )
    (net (code "67") (name "Net-(K3A-P)") (class "Default")
      (node (ref "K3") (pin "4") (pinfunction "P_4") (pintype "passive"))
      (node (ref "R30") (pin "2") (pinfunction "2_2") (pintype "passive"))
    )
    (net (code "68") (name "Net-(K3A-S)") (class "Default")
      (node (ref "ADI1") (pin "3") (pinfunction "3_3") (pintype "passive"))
      (node (ref "K3") (pin "8") (pinfunction "S_8") (pintype "passive"))
    )
    (net (code "69") (name "Net-(K3B-P)") (class "Default")
      (node (ref "K3") (pin "13") (pinfunction "P_13") (pintype "passive"))
      (node (ref "R29") (pin "2") (pinfunction "2_2") (pintype "passive"))
    )
    (net (code "70") (name "Net-(K3B-S)") (class "Default")
      (node (ref "ADI1") (pin "1") (pinfunction "1_1") (pintype "passive"))
      (node (ref "K3") (pin "9") (pinfunction "S_9") (pintype "passive"))
    )
    (net (code "71") (name "Net-(K4A-P)") (class "Default")
      (node (ref "K4") (pin "4") (pinfunction "P_4") (pintype "passive"))
      (node (ref "R32") (pin "2") (pinfunction "2_2") (pintype "passive"))
    )
    (net (code "72") (name "Net-(K4A-S)") (class "Default")
      (node (ref "ADI1") (pin "7") (pinfunction "7_7") (pintype "passive"))
      (node (ref "K4") (pin "8") (pinfunction "S_8") (pintype "passive"))
    )
    (net (code "73") (name "Net-(K4B-P)") (class "Default")
      (node (ref "K4") (pin "13") (pinfunction "P_13") (pintype "passive"))
      (node (ref "R31") (pin "2") (pinfunction "2_2") (pintype "passive"))
    )
    (net (code "74") (name "Net-(K4B-S)") (class "Default")
      (node (ref "ADI1") (pin "5") (pinfunction "5_5") (pintype "passive"))
      (node (ref "K4") (pin "9") (pinfunction "S_9") (pintype "passive"))
    )
    (net (code "75") (name "Net-(LED-C)") (class "Default")
      (node (ref "LED") (pin "K") (pinfunction "C_K") (pintype "passive"))
      (node (ref "R37") (pin "2") (pinfunction "2_2") (pintype "passive"))
    )
    (net (code "76") (name "Net-(R1-Pad1)") (class "Default")
      (node (ref "R1") (pin "1") (pinfunction "1_1") (pintype "passive"))
      (node (ref "SV1") (pin "4") (pinfunction "4_4") (pintype "passive"))
    )
    (net (code "77") (name "Net-(R2-Pad1)") (class "Default")
      (node (ref "R2") (pin "1") (pinfunction "1_1") (pintype "passive"))
      (node (ref "SV1") (pin "3") (pinfunction "3_3") (pintype "passive"))
    )
    (net (code "78") (name "Net-(R3-E)") (class "Default")
      (node (ref "R3") (pin "3") (pinfunction "E_3") (pintype "passive"))
      (node (ref "SYNP") (pin "4") (pinfunction "4_4") (pintype "passive"))
    )
    (net (code "79") (name "Net-(R3-S)") (class "Default")
      (node (ref "R3") (pin "2") (pinfunction "S_2") (pintype "passive"))
      (node (ref "R47") (pin "2") (pinfunction "2_2") (pintype "passive"))
    )
    (net (code "80") (name "Net-(R4-E)") (class "Default")
      (node (ref "R4") (pin "3") (pinfunction "E_3") (pintype "passive"))
      (node (ref "SYNR") (pin "4") (pinfunction "4_4") (pintype "passive"))
    )
    (net (code "81") (name "Net-(R4-S)") (class "Default")
      (node (ref "R38") (pin "2") (pinfunction "2_2") (pintype "passive"))
      (node (ref "R4") (pin "2") (pinfunction "S_2") (pintype "passive"))
    )
    (net (code "82") (name "Net-(R7-E)") (class "Default")
      (node (ref "R7") (pin "3") (pinfunction "E_3") (pintype "passive"))
      (node (ref "SYNR") (pin "3") (pinfunction "3_3") (pintype "passive"))
    )
    (net (code "83") (name "Net-(R7-S)") (class "Default")
      (node (ref "R41") (pin "2") (pinfunction "2_2") (pintype "passive"))
      (node (ref "R7") (pin "2") (pinfunction "S_2") (pintype "passive"))
    )
    (net (code "84") (name "Net-(R8-E)") (class "Default")
      (node (ref "R8") (pin "3") (pinfunction "E_3") (pintype "passive"))
      (node (ref "SYNP") (pin "3") (pinfunction "3_3") (pintype "passive"))
    )
    (net (code "85") (name "Net-(R8-S)") (class "Default")
      (node (ref "R50") (pin "2") (pinfunction "2_2") (pintype "passive"))
      (node (ref "R8") (pin "2") (pinfunction "S_2") (pintype "passive"))
    )
    (net (code "86") (name "Net-(R10-Pad1)") (class "Default")
      (node (ref "R10") (pin "1") (pinfunction "1_1") (pintype "passive"))
      (node (ref "SV2") (pin "5") (pinfunction "5_5") (pintype "passive"))
    )
    (net (code "87") (name "Net-(R13-S)") (class "Default")
      (node (ref "R13") (pin "2") (pinfunction "S_2") (pintype "passive"))
      (node (ref "R9") (pin "2") (pinfunction "2_2") (pintype "passive"))
    )
    (net (code "88") (name "Net-(R14-E)") (class "Default")
      (node (ref "R14") (pin "3") (pinfunction "E_3") (pintype "passive"))
      (node (ref "SYNR") (pin "2") (pinfunction "2_2") (pintype "passive"))
    )
    (net (code "89") (name "Net-(R14-S)") (class "Default")
      (node (ref "R14") (pin "2") (pinfunction "S_2") (pintype "passive"))
      (node (ref "R44") (pin "2") (pinfunction "2_2") (pintype "passive"))
    )
    (net (code "90") (name "Net-(R15-E)") (class "Default")
      (node (ref "R15") (pin "3") (pinfunction "E_3") (pintype "passive"))
      (node (ref "SYNP") (pin "2") (pinfunction "2_2") (pintype "passive"))
    )
    (net (code "91") (name "Net-(R15-S)") (class "Default")
      (node (ref "R15") (pin "2") (pinfunction "S_2") (pintype "passive"))
      (node (ref "R53") (pin "2") (pinfunction "2_2") (pintype "passive"))
    )
    (net (code "92") (name "Net-(R21-S)") (class "Default")
      (node (ref "R16") (pin "2") (pinfunction "2_2") (pintype "passive"))
      (node (ref "R21") (pin "2") (pinfunction "S_2") (pintype "passive"))
    )
    (net (code "93") (name "Net-(R22-S)") (class "Default")
      (node (ref "R18") (pin "2") (pinfunction "2_2") (pintype "passive"))
      (node (ref "R22") (pin "2") (pinfunction "S_2") (pintype "passive"))
    )
    (net (code "94") (name "unconnected-(IC1-O3-Pad16)") (class "Default")
      (node (ref "IC1") (pin "16") (pinfunction "O3_16") (pintype "open_collector"))
    )
    (net (code "95") (name "unconnected-(K1A-O-Pad6)") (class "Default")
      (node (ref "K1") (pin "6") (pinfunction "O_6") (pintype "passive"))
    )
    (net (code "96") (name "unconnected-(K1B-O-Pad11)") (class "Default")
      (node (ref "K1") (pin "11") (pinfunction "O_11") (pintype "passive"))
    )
    (net (code "97") (name "unconnected-(K2A-O-Pad6)") (class "Default")
      (node (ref "K2") (pin "6") (pinfunction "O_6") (pintype "passive"))
    )
    (net (code "98") (name "unconnected-(K2B-O-Pad11)") (class "Default")
      (node (ref "K2") (pin "11") (pinfunction "O_11") (pintype "passive"))
    )
    (net (code "99") (name "unconnected-(K3A-O-Pad6)") (class "Default")
      (node (ref "K3") (pin "6") (pinfunction "O_6") (pintype "passive"))
    )
    (net (code "100") (name "unconnected-(K3B-O-Pad11)") (class "Default")
      (node (ref "K3") (pin "11") (pinfunction "O_11") (pintype "passive"))
    )
    (net (code "101") (name "unconnected-(K4A-O-Pad6)") (class "Default")
      (node (ref "K4") (pin "6") (pinfunction "O_6") (pintype "passive"))
    )
    (net (code "102") (name "unconnected-(K4B-O-Pad11)") (class "Default")
      (node (ref "K4") (pin "11") (pinfunction "O_11") (pintype "passive"))
    )
    (net (code "103") (name "unconnected-(TMR3-2421-ON{slash}OFF-Pad3)") (class "Default")
      (node (ref "TMR3-2421") (pin "3") (pinfunction "ON/OFF_3") (pintype "passive"))
    )
    (net (code "104") (name "unconnected-(TMR3-2422-ON{slash}OFF-Pad3)") (class "Default")
      (node (ref "TMR3-2422") (pin "3") (pinfunction "ON/OFF_3") (pintype "passive"))
    )
  )
)
